# Hscope_402.net
KiCad netlist of a schematic drawn in EAGLE
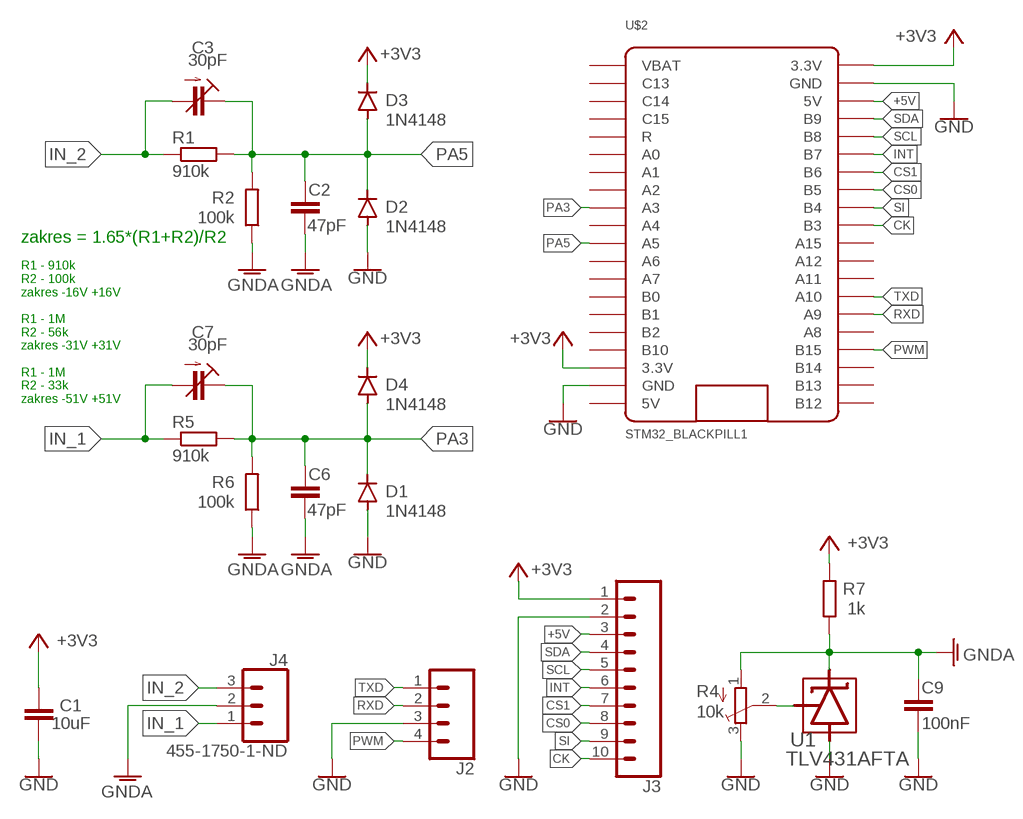
[diagram p0: schematic, sheet 1]

(export (version "E")
  (design (tool "Eeschema 10.0.6"))
  (components
    (comp (ref "C1")
      (value "10uF")
      (footprint "eagle-import:C0805")
      (libsource (lib "eagle-import") (part "C-EUC0805"))
    )
    (comp (ref "C2")
      (value "47pF")
      (footprint "eagle-import:C0805")
      (libsource (lib "eagle-import") (part "C-EUC0805"))
    )
    (comp (ref "C3")
      (value "30pF")
      (footprint "eagle-import:CTRIM3018_12")
      (libsource (lib "eagle-import") (part "C-TRIMM3018_12"))
    )
    (comp (ref "C6")
      (value "47pF")
      (footprint "eagle-import:C0805")
      (libsource (lib "eagle-import") (part "C-EUC0805"))
    )
    (comp (ref "C7")
      (value "30pF")
      (footprint "eagle-import:CTRIM3018_12")
      (libsource (lib "eagle-import") (part "C-TRIMM3018_12"))
    )
    (comp (ref "C9")
      (value "100nF")
      (footprint "eagle-import:C0805")
      (libsource (lib "eagle-import") (part "C-EUC0805"))
    )
    (comp (ref "D1")
      (value "1N4148")
      (footprint "eagle-import:SOD323-W")
      (libsource (lib "eagle-import") (part "DIODE-SOD323-W"))
    )
    (comp (ref "D2")
      (value "1N4148")
      (footprint "eagle-import:SOD323-W")
      (libsource (lib "eagle-import") (part "DIODE-SOD323-W"))
    )
    (comp (ref "D3")
      (value "1N4148")
      (footprint "eagle-import:SOD323-W")
      (libsource (lib "eagle-import") (part "DIODE-SOD323-W"))
    )
    (comp (ref "D4")
      (value "1N4148")
      (footprint "eagle-import:SOD323-W")
      (libsource (lib "eagle-import") (part "DIODE-SOD323-W"))
    )
    (comp (ref "J2")
      (value "CONN_04PTH")
      (footprint "eagle-import:1X04")
      (libsource (lib "eagle-import") (part "CONN_04PTH"))
    )
    (comp (ref "J3")
      (value "CONN_10\"")
      (footprint "eagle-import:1X10")
      (libsource (lib "eagle-import") (part "CONN_10{dblquote}"))
    )
    (comp (ref "J4")
      (value "455-1750-1-ND")
      (footprint "eagle-import:1X03")
      (libsource (lib "eagle-import") (part "CONN_03"))
    )
    (comp (ref "R1")
      (value "910k")
      (footprint "eagle-import:R0805")
      (libsource (lib "eagle-import") (part "R-EU_R0805"))
    )
    (comp (ref "R2")
      (value "100k")
      (footprint "eagle-import:R0805")
      (libsource (lib "eagle-import") (part "R-EU_R0805"))
    )
    (comp (ref "R4")
      (value "10k")
      (footprint "eagle-import:SM-42_43A")
      (libsource (lib "eagle-import") (part "TRIM_EU-SM-42/43A"))
    )
    (comp (ref "R5")
      (value "910k")
      (footprint "eagle-import:R0805")
      (libsource (lib "eagle-import") (part "R-EU_R0805"))
    )
    (comp (ref "R6")
      (value "100k")
      (footprint "eagle-import:R0805")
      (libsource (lib "eagle-import") (part "R-EU_R0805"))
    )
    (comp (ref "R7")
      (value "1k")
      (footprint "eagle-import:R0805")
      (libsource (lib "eagle-import") (part "R-EU_R0805"))
    )
    (comp (ref "U$2")
      (value "STM32_BLACKPILL1")
      (footprint "eagle-import:STM32_BLACKPILL")
      (libsource (lib "eagle-import") (part "STM32_BLACKPILL1"))
    )
    (comp (ref "U1")
      (value "TLV431AFTA")
      (footprint "eagle-import:SOT95P237X112-3N")
      (libsource (lib "eagle-import") (part "TLV431AFTA"))
    )
  )
  (nets
    (net (code "1") (name "+3V3") (class "Default")
      (node (ref "C1") (pin "2") (pinfunction "2_2") (pintype "passive"))
      (node (ref "D3") (pin "C") (pinfunction "C_C") (pintype "passive"))
      (node (ref "D4") (pin "C") (pinfunction "C_C") (pintype "passive"))
      (node (ref "J3") (pin "1") (pinfunction "1_1") (pintype "passive"))
      (node (ref "R7") (pin "2") (pinfunction "2_2") (pintype "passive"))
      (node (ref "U$2") (pin "P$20") (pinfunction "3.3V_P$20") (pintype "power_in"))
      (node (ref "U$2") (pin "P$23") (pinfunction "3.3V_P$23") (pintype "power_in"))
    )
    (net (code "2") (name "+5V") (class "Default")
      (node (ref "J3") (pin "3") (pinfunction "3_3") (pintype "passive"))
      (node (ref "U$2") (pin "P$18") (pinfunction "5V_P$18") (pintype "power_in"))
    )
    (net (code "3") (name "/5V") (class "Default")
      (node (ref "U$2") (pin "P$21") (pinfunction "5V_P$21") (pintype "power_in"))
    )
    (net (code "4") (name "/VBAT") (class "Default")
      (node (ref "U$2") (pin "P$40") (pinfunction "VBAT_P$40") (pintype "power_in"))
    )
    (net (code "5") (name "CK") (class "Default")
      (node (ref "J3") (pin "10") (pinfunction "10_10") (pintype "passive"))
      (node (ref "U$2") (pin "P$11") (pinfunction "B3_P$11") (pintype "bidirectional"))
    )
    (net (code "6") (name "CS0") (class "Default")
      (node (ref "J3") (pin "8") (pinfunction "8_8") (pintype "passive"))
      (node (ref "U$2") (pin "P$13") (pinfunction "B5_P$13") (pintype "bidirectional"))
    )
    (net (code "7") (name "CS1") (class "Default")
      (node (ref "J3") (pin "7") (pinfunction "7_7") (pintype "passive"))
      (node (ref "U$2") (pin "P$14") (pinfunction "B6_P$14") (pintype "bidirectional"))
    )
    (net (code "8") (name "GND") (class "Default")
      (node (ref "C1") (pin "1") (pinfunction "1_1") (pintype "passive"))
      (node (ref "C9") (pin "1") (pinfunction "1_1") (pintype "passive"))
      (node (ref "D1") (pin "A") (pinfunction "A_A") (pintype "passive"))
      (node (ref "D2") (pin "A") (pinfunction "A_A") (pintype "passive"))
      (node (ref "J2") (pin "3") (pinfunction "3_3") (pintype "passive"))
      (node (ref "J3") (pin "2") (pinfunction "2_2") (pintype "passive"))
      (node (ref "R4") (pin "3") (pinfunction "E_3") (pintype "passive"))
      (node (ref "U$2") (pin "P$19") (pinfunction "GND_P$19") (pintype "power_in"))
      (node (ref "U$2") (pin "P$22") (pinfunction "GND_P$22") (pintype "power_in"))
      (node (ref "U1") (pin "3") (pinfunction "ANODE_3") (pintype "passive"))
    )
    (net (code "9") (name "GNDA") (class "Default")
      (node (ref "C2") (pin "1") (pinfunction "1_1") (pintype "passive"))
      (node (ref "C6") (pin "1") (pinfunction "1_1") (pintype "passive"))
      (node (ref "C9") (pin "2") (pinfunction "2_2") (pintype "passive"))
      (node (ref "J4") (pin "2") (pinfunction "2_2") (pintype "passive"))
      (node (ref "R2") (pin "1") (pinfunction "1_1") (pintype "passive"))
      (node (ref "R4") (pin "1") (pinfunction "A_1") (pintype "passive"))
      (node (ref "R6") (pin "1") (pinfunction "1_1") (pintype "passive"))
      (node (ref "R7") (pin "1") (pinfunction "1_1") (pintype "passive"))
      (node (ref "U1") (pin "2") (pinfunction "CATHODE_2") (pintype "passive"))
    )
    (net (code "10") (name "INT") (class "Default")
      (node (ref "J3") (pin "6") (pinfunction "6_6") (pintype "passive"))
      (node (ref "U$2") (pin "P$15") (pinfunction "B7_P$15") (pintype "bidirectional"))
    )
    (net (code "11") (name "IN_1") (class "Default")
      (node (ref "C7") (pin "-") (pinfunction "A_-") (pintype "passive"))
      (node (ref "J4") (pin "1") (pinfunction "1_1") (pintype "passive"))
      (node (ref "R5") (pin "1") (pinfunction "1_1") (pintype "passive"))
    )
    (net (code "12") (name "IN_2") (class "Default")
      (node (ref "C3") (pin "-") (pinfunction "A_-") (pintype "passive"))
      (node (ref "J4") (pin "3") (pinfunction "3_3") (pintype "passive"))
      (node (ref "R1") (pin "1") (pinfunction "1_1") (pintype "passive"))
    )
    (net (code "13") (name "Net-(R4-S)") (class "Default")
      (node (ref "R4") (pin "2") (pinfunction "S_2") (pintype "passive"))
      (node (ref "U1") (pin "1") (pinfunction "REF_1") (pintype "passive"))
    )
    (net (code "14") (name "PA3") (class "Default")
      (node (ref "C6") (pin "2") (pinfunction "2_2") (pintype "passive"))
      (node (ref "C7") (pin "+") (pinfunction "E_+") (pintype "passive"))
      (node (ref "D1") (pin "C") (pinfunction "C_C") (pintype "passive"))
      (node (ref "D4") (pin "A") (pinfunction "A_A") (pintype "passive"))
      (node (ref "R5") (pin "2") (pinfunction "2_2") (pintype "passive"))
      (node (ref "R6") (pin "2") (pinfunction "2_2") (pintype "passive"))
      (node (ref "U$2") (pin "P$32") (pinfunction "A3_P$32") (pintype "bidirectional"))
    )
    (net (code "15") (name "PA5") (class "Default")
      (node (ref "C2") (pin "2") (pinfunction "2_2") (pintype "passive"))
      (node (ref "C3") (pin "+") (pinfunction "E_+") (pintype "passive"))
      (node (ref "D2") (pin "C") (pinfunction "C_C") (pintype "passive"))
      (node (ref "D3") (pin "A") (pinfunction "A_A") (pintype "passive"))
      (node (ref "R1") (pin "2") (pinfunction "2_2") (pintype "passive"))
      (node (ref "R2") (pin "2") (pinfunction "2_2") (pintype "passive"))
      (node (ref "U$2") (pin "P$30") (pinfunction "A5_P$30") (pintype "bidirectional"))
    )
    (net (code "16") (name "PWM") (class "Default")
      (node (ref "J2") (pin "4") (pinfunction "4_4") (pintype "passive"))
      (node (ref "U$2") (pin "P$4") (pinfunction "B15_P$4") (pintype "bidirectional"))
    )
    (net (code "17") (name "RXD") (class "Default")
      (node (ref "J2") (pin "2") (pinfunction "2_2") (pintype "passive"))
      (node (ref "U$2") (pin "P$6") (pinfunction "A9_P$6") (pintype "bidirectional"))
    )
    (net (code "18") (name "SCL") (class "Default")
      (node (ref "J3") (pin "5") (pinfunction "5_5") (pintype "passive"))
      (node (ref "U$2") (pin "P$16") (pinfunction "B8_P$16") (pintype "bidirectional"))
    )
    (net (code "19") (name "SDA") (class "Default")
      (node (ref "J3") (pin "4") (pinfunction "4_4") (pintype "passive"))
      (node (ref "U$2") (pin "P$17") (pinfunction "B9_P$17") (pintype "bidirectional"))
    )
    (net (code "20") (name "SI") (class "Default")
      (node (ref "J3") (pin "9") (pinfunction "9_9") (pintype "passive"))
      (node (ref "U$2") (pin "P$12") (pinfunction "B4_P$12") (pintype "bidirectional"))
    )
    (net (code "21") (name "TXD") (class "Default")
      (node (ref "J2") (pin "1") (pinfunction "1_1") (pintype "passive"))
      (node (ref "U$2") (pin "P$7") (pinfunction "A10_P$7") (pintype "bidirectional"))
    )
    (net (code "22") (name "unconnected-(U$2-A0-PadP$35)") (class "Default")
      (node (ref "U$2") (pin "P$35") (pinfunction "A0_P$35") (pintype "bidirectional"))
    )
    (net (code "23") (name "unconnected-(U$2-A1-PadP$34)") (class "Default")
      (node (ref "U$2") (pin "P$34") (pinfunction "A1_P$34") (pintype "bidirectional"))
    )
    (net (code "24") (name "unconnected-(U$2-A2-PadP$33)") (class "Default")
      (node (ref "U$2") (pin "P$33") (pinfunction "A2_P$33") (pintype "bidirectional"))
    )
    (net (code "25") (name "unconnected-(U$2-A4-PadP$31)") (class "Default")
      (node (ref "U$2") (pin "P$31") (pinfunction "A4_P$31") (pintype "bidirectional"))
    )
    (net (code "26") (name "unconnected-(U$2-A6-PadP$29)") (class "Default")
      (node (ref "U$2") (pin "P$29") (pinfunction "A6_P$29") (pintype "bidirectional"))
    )
    (net (code "27") (name "unconnected-(U$2-A7-PadP$28)") (class "Default")
      (node (ref "U$2") (pin "P$28") (pinfunction "A7_P$28") (pintype "bidirectional"))
    )
    (net (code "28") (name "unconnected-(U$2-A8-PadP$5)") (class "Default")
      (node (ref "U$2") (pin "P$5") (pinfunction "A8_P$5") (pintype "bidirectional"))
    )
    (net (code "29") (name "unconnected-(U$2-A11-PadP$8)") (class "Default")
      (node (ref "U$2") (pin "P$8") (pinfunction "A11_P$8") (pintype "bidirectional"))
    )
    (net (code "30") (name "unconnected-(U$2-A12-PadP$9)") (class "Default")
      (node (ref "U$2") (pin "P$9") (pinfunction "A12_P$9") (pintype "bidirectional"))
    )
    (net (code "31") (name "unconnected-(U$2-A15-PadP$10)") (class "Default")
      (node (ref "U$2") (pin "P$10") (pinfunction "A15_P$10") (pintype "bidirectional"))
    )
    (net (code "32") (name "unconnected-(U$2-B0-PadP$27)") (class "Default")
      (node (ref "U$2") (pin "P$27") (pinfunction "B0_P$27") (pintype "bidirectional"))
    )
    (net (code "33") (name "unconnected-(U$2-B1-PadP$26)") (class "Default")
      (node (ref "U$2") (pin "P$26") (pinfunction "B1_P$26") (pintype "bidirectional"))
    )
    (net (code "34") (name "unconnected-(U$2-B2-PadP$25)") (class "Default")
      (node (ref "U$2") (pin "P$25") (pinfunction "B2_P$25") (pintype "bidirectional"))
    )
    (net (code "35") (name "unconnected-(U$2-B10-PadP$24)") (class "Default")
      (node (ref "U$2") (pin "P$24") (pinfunction "B10_P$24") (pintype "bidirectional"))
    )
    (net (code "36") (name "unconnected-(U$2-B12-PadP$1)") (class "Default")
      (node (ref "U$2") (pin "P$1") (pinfunction "B12_P$1") (pintype "bidirectional"))
    )
    (net (code "37") (name "unconnected-(U$2-B13-PadP$2)") (class "Default")
      (node (ref "U$2") (pin "P$2") (pinfunction "B13_P$2") (pintype "bidirectional"))
    )
    (net (code "38") (name "unconnected-(U$2-B14-PadP$3)") (class "Default")
      (node (ref "U$2") (pin "P$3") (pinfunction "B14_P$3") (pintype "bidirectional"))
    )
    (net (code "39") (name "unconnected-(U$2-C13-PadP$39)") (class "Default")
      (node (ref "U$2") (pin "P$39") (pinfunction "C13_P$39") (pintype "bidirectional"))
    )
    (net (code "40") (name "unconnected-(U$2-C14-PadP$38)") (class "Default")
      (node (ref "U$2") (pin "P$38") (pinfunction "C14_P$38") (pintype "bidirectional"))
    )
    (net (code "41") (name "unconnected-(U$2-C15-PadP$37)") (class "Default")
      (node (ref "U$2") (pin "P$37") (pinfunction "C15_P$37") (pintype "bidirectional"))
    )
    (net (code "42") (name "unconnected-(U$2-R-PadP$36)") (class "Default")
      (node (ref "U$2") (pin "P$36") (pinfunction "R_P$36") (pintype "bidirectional"))
    )
  )
)
